# User_-_User_Interface.net
KiCad netlist of a schematic drawn in Altium Designer
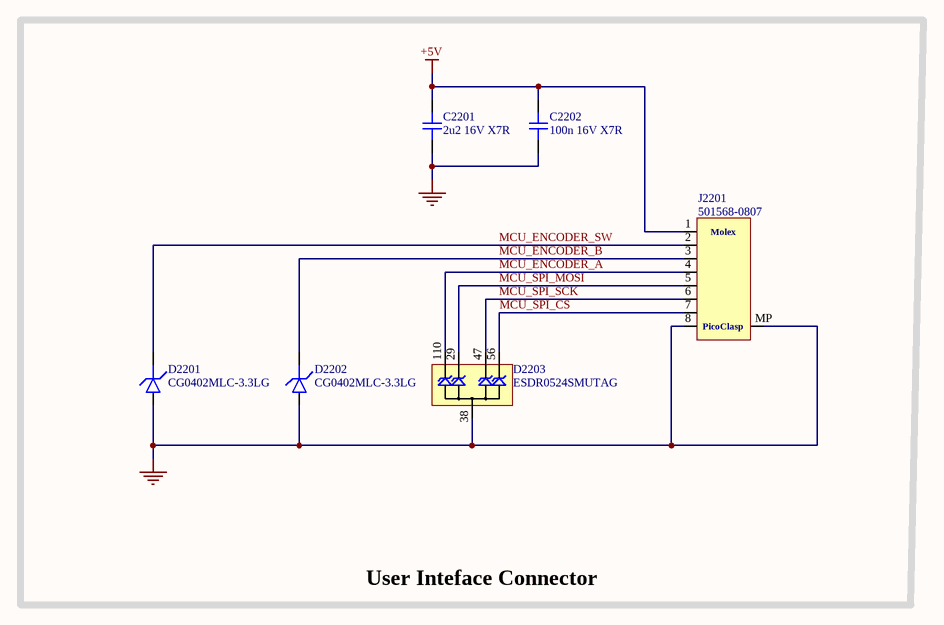
[diagram p0: User - User Interface.SchDoc]

(export (version "E")
  (design (tool "Eeschema 10.0.6"))
  (components
    (comp (ref "C2201")
      (value "2u2 16V X7R")
      (footprint "CAP_0603")
      (description "Capacitor SMD 0603")
      (fields
        (field (name "MANUFACTURER") "YAGEO")
        (field (name "MANUFACTURER PART NUMBER") "CC0603KRX7R7BB225")
      )
      (libsource (lib "Schematic-Lib-PhilsLab") (part "CAP_0603"))
    )
    (comp (ref "C2202")
      (value "100n 16V X7R")
      (footprint "CAP_0402")
      (description "Capacitor SMD 0402")
      (fields
        (field (name "MANUFACTURER") "YAGEO")
        (field (name "MANUFACTURER PART NUMBER") "CC0402JRX7R7BB104")
      )
      (libsource (lib "Schematic-Lib-PhilsLab") (part "CAP_0402"))
    )
    (comp (ref "D2201")
      (value "CG0402MLC-3.3LG")
      (footprint "D_0402")
      (description "Diode TVS / ESD 0402")
      (libsource (lib "Schematic-Lib-PhilsLab") (part "D_TVS_0402"))
    )
    (comp (ref "D2202")
      (value "CG0402MLC-3.3LG")
      (footprint "D_0402")
      (description "Diode TVS / ESD 0402")
      (libsource (lib "Schematic-Lib-PhilsLab") (part "D_TVS_0402"))
    )
    (comp (ref "D2203")
      (value "ESDR0524SMUTAG")
      (footprint "uDFN-10-WIDE")
      (description "TVS Diode Array Low Capacitance ESD Protection 4-Channel (Vwork=5V, Vclamp=15V)")
      (fields (field (name "MANUFACTURER") "onsemi"))
      (libsource (lib "Schematic-Lib-PhilsLab") (part "ESDR0524SMUTAG"))
    )
    (comp (ref "J2201")
      (value "501568-0807")
      (footprint "501568-0807")
      (fields (field (name "MANUFACTURER") "Molex"))
      (libsource (lib "Schematic-Lib-PhilsLab") (part "501568-0807"))
    )
  )
  (nets
    (net (code "1") (name "+5V") (class "Default")
      (node (ref "C2201") (pin "2") (pinfunction "2_2") (pintype "passive"))
      (node (ref "C2202") (pin "2") (pinfunction "2_2") (pintype "passive"))
      (node (ref "J2201") (pin "1") (pinfunction "1_1") (pintype "passive"))
    )
    (net (code "2") (name "/MCU_ENCODER_A") (class "Default")
      (node (ref "D2203") (pin "110") (pintype "passive"))
      (node (ref "J2201") (pin "4") (pinfunction "4_4") (pintype "passive"))
    )
    (net (code "3") (name "/MCU_ENCODER_B") (class "Default")
      (node (ref "D2202") (pin "K") (pinfunction "K_K") (pintype "passive"))
      (node (ref "J2201") (pin "3") (pinfunction "3_3") (pintype "passive"))
    )
    (net (code "4") (name "/MCU_ENCODER_SW") (class "Default")
      (node (ref "D2201") (pin "K") (pinfunction "K_K") (pintype "passive"))
      (node (ref "J2201") (pin "2") (pinfunction "2_2") (pintype "passive"))
    )
    (net (code "5") (name "/MCU_SPI_CS") (class "Default")
      (node (ref "D2203") (pin "56") (pintype "passive"))
      (node (ref "J2201") (pin "7") (pinfunction "7_7") (pintype "passive"))
    )
    (net (code "6") (name "/MCU_SPI_MOSI") (class "Default")
      (node (ref "D2203") (pin "29") (pintype "passive"))
      (node (ref "J2201") (pin "5") (pinfunction "5_5") (pintype "passive"))
    )
    (net (code "7") (name "/MCU_SPI_SCK") (class "Default")
      (node (ref "D2203") (pin "47") (pintype "passive"))
      (node (ref "J2201") (pin "6") (pinfunction "6_6") (pintype "passive"))
    )
    (net (code "8") (name "GND") (class "Default")
      (node (ref "C2201") (pin "1") (pinfunction "1_1") (pintype "passive"))
      (node (ref "C2202") (pin "1") (pinfunction "1_1") (pintype "passive"))
      (node (ref "D2201") (pin "A") (pinfunction "A_A") (pintype "passive"))
      (node (ref "D2202") (pin "A") (pinfunction "A_A") (pintype "passive"))
      (node (ref "D2203") (pin "38") (pinfunction "GND_38") (pintype "passive"))
      (node (ref "J2201") (pin "8") (pinfunction "8_8") (pintype "passive"))
      (node (ref "J2201") (pin "MP") (pinfunction "MP_MP") (pintype "passive"))
    )
  )
)
